# zb_pic16f887.net
KiCad netlist of a schematic drawn in Altium Designer
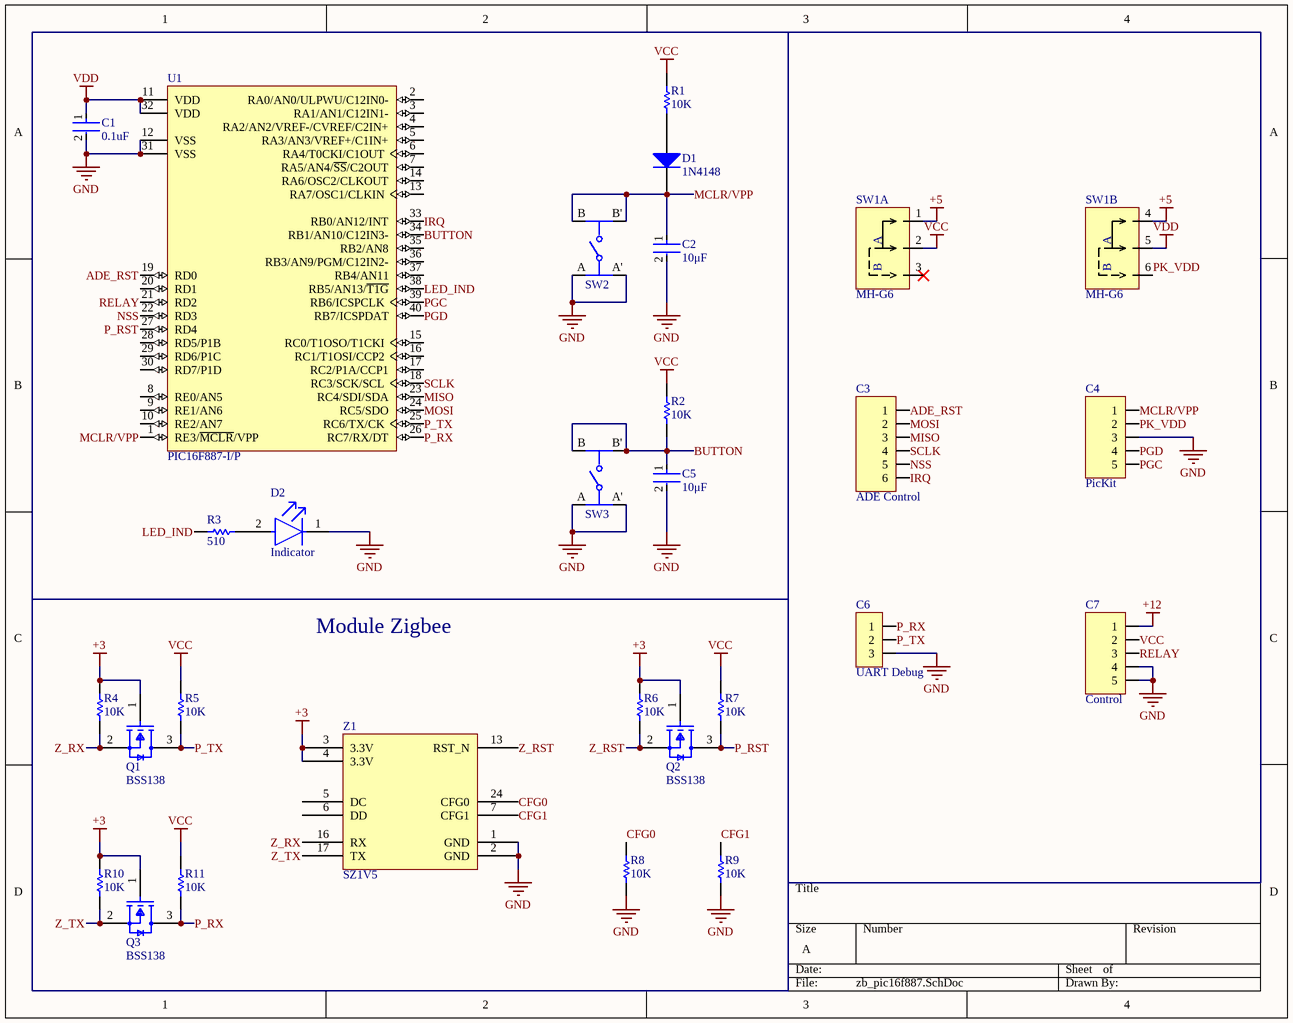
[diagram p0: zb_pic16f887.SchDoc]

(export (version "E")
  (design (tool "Eeschema 10.0.6"))
  (components
    (comp (ref "C1")
      (value "0.1uF")
      (footprint "FP-0603-L_1_6_0_15-W_0_81-IPC_A")
      (description "General Purpose Ceramic Capacitor, 0603, 100nF, 10%, X7R, 15%, 50V")
      (fields (field (name "TOLERANCE") "10%") (field (name "VOLTAGE") "50V"))
      (libsource (lib "Altium Content Vault") (part "02cd4be3c70576c341d710602a673aa"))
    )
    (comp (ref "C2")
      (value "10μF")
      (footprint "FP-0603-L_1_6_0_15-W_0_81-IPC_A")
      (description "General Purpose Ceramic Capacitor, 0603, 100nF, 10%, X7R, 15%, 50V")
      (fields (field (name "TOLERANCE") "10%") (field (name "VOLTAGE") "50V"))
      (libsource (lib "Altium Content Vault") (part "02cd4be3c70576c341d710602a673aa"))
    )
    (comp (ref "C3")
      (value "ADE Control")
      (footprint "JP6-D1T")
      (description "WR-PHD 2.54 mm Angled Socket Header")
      (fields
        (field (name "MANUFACTURER") "Würth Elektronik eiSos GmbH")
        (field (name "PARTNO") "613006143121")
        (field (name "CREATED BY") "Karrer Zheng")
      )
      (libsource (lib "TechMT.VN_Lib_Project v2") (part "JP6"))
    )
    (comp (ref "C4")
      (value "PicKit")
      (footprint "JP5-D1C")
      (description "WR-PHD 2.54 mm Angled Socket Header")
      (fields
        (field (name "MANUFACTURER") "Würth Elektronik eiSos GmbH")
        (field (name "PARTNO") "613005143121")
        (field (name "CREATED BY") "Karrer Zheng")
      )
      (libsource (lib "TechMT.VN_Lib_Project v2") (part "JP5"))
    )
    (comp (ref "C5")
      (value "10μF")
      (footprint "FP-0603-L_1_6_0_15-W_0_81-IPC_A")
      (description "General Purpose Ceramic Capacitor, 0603, 100nF, 10%, X7R, 15%, 50V")
      (fields (field (name "TOLERANCE") "10%") (field (name "VOLTAGE") "50V"))
      (libsource (lib "Altium Content Vault") (part "02cd4be3c70576c341d710602a673aa"))
    )
    (comp (ref "C6")
      (value "UART Debug")
      (footprint "JP3-D1C")
      (description "WR-PHD 2.54 mm Angled Socket Header")
      (fields
        (field (name "MANUFACTURER") "Würth Elektronik eiSos GmbH")
        (field (name "PARTNO") "613003143121")
        (field (name "CREATED BY") "Karrer Zheng")
      )
      (libsource (lib "TechMT.VN_Lib_Project v2") (part "JP3"))
    )
    (comp (ref "C7")
      (value "Control")
      (footprint "JP5-D1T")
      (description "WR-PHD 2.54 mm Angled Socket Header")
      (fields
        (field (name "MANUFACTURER") "Würth Elektronik eiSos GmbH")
        (field (name "PARTNO") "613005143121")
        (field (name "CREATED BY") "Karrer Zheng")
      )
      (libsource (lib "TechMT.VN_Lib_Project v2") (part "JP5"))
    )
    (comp (ref "D1")
      (value "1N4148")
      (footprint "NXP-SOD27-2_V")
      (description "High-speed Diode, 100 V, 450 mA, 2-Pin SOD27, RoHS")
      (fields (field (name "MANUFACTURER") "NXP Semiconductors"))
      (libsource (lib "Altium Content Vault") (part "NXP-A1K2-2"))
    )
    (comp (ref "D2")
      (value "Indicator")
      (footprint "FP-HLMP-4700-MFG")
      (description "LED RED DIFFUSED T-1 3/4 T/H")
      (fields
        (field (name "OCTOPART") "https://octopart.com/hlmp-4700-broadcom-71130526")
        (field (name "MANUFACTURER") "Broadcom")
      )
      (libsource (lib "Altium Content Vault") (part "8706943c75ba83719d021d2fdc84c58"))
    )
    (comp (ref "Q1")
      (value "BSS138")
      (footprint "FP-318-08-IPC_B")
      (description "MOSFET N-CH 50V 220MA SOT-23")
      (libsource (lib "Altium Content Vault") (part "3b9c635fedb024a5347a57b145af9cc"))
    )
    (comp (ref "Q2")
      (value "BSS138")
      (footprint "FP-318-08-IPC_B")
      (description "MOSFET N-CH 50V 220MA SOT-23")
      (libsource (lib "Altium Content Vault") (part "3b9c635fedb024a5347a57b145af9cc"))
    )
    (comp (ref "Q3")
      (value "BSS138")
      (footprint "FP-318-08-IPC_B")
      (description "MOSFET N-CH 50V 220MA SOT-23")
      (libsource (lib "Altium Content Vault") (part "3b9c635fedb024a5347a57b145af9cc"))
    )
    (comp (ref "R1")
      (value "10K")
      (footprint "RESC1609X55X30ML15T15")
      (description "Chip Resistor, 10 KOhm, +/- 1%, 0.1 W, -55 to 155 degC, 0603 (1608 Metric), RoHS, Tape and Reel")
      (fields (field (name "TOLERANCE") "1%") (field (name "MANUFACTURER") "Panasonic"))
      (libsource (lib "Altium Content Vault") (part "RES-2"))
    )
    (comp (ref "R2")
      (value "10K")
      (footprint "RESC1609X55X30ML15T15")
      (description "Chip Resistor, 10 KOhm, +/- 1%, 0.1 W, -55 to 155 degC, 0603 (1608 Metric), RoHS, Tape and Reel")
      (fields (field (name "TOLERANCE") "1%") (field (name "MANUFACTURER") "Panasonic"))
      (libsource (lib "Altium Content Vault") (part "RES-2"))
    )
    (comp (ref "R3")
      (value "510")
      (footprint "RESC1609X55X30ML15T15")
      (description "Chip Resistor, 10 KOhm, +/- 1%, 0.1 W, -55 to 155 degC, 0603 (1608 Metric), RoHS, Tape and Reel")
      (fields (field (name "TOLERANCE") "1%") (field (name "MANUFACTURER") "Panasonic"))
      (libsource (lib "Altium Content Vault") (part "RES-2"))
    )
    (comp (ref "R4")
      (value "10K")
      (footprint "RESC1609X55X30ML15T15")
      (description "Chip Resistor, 10 KOhm, +/- 1%, 0.1 W, -55 to 155 degC, 0603 (1608 Metric), RoHS, Tape and Reel")
      (fields (field (name "TOLERANCE") "1%") (field (name "MANUFACTURER") "Panasonic"))
      (libsource (lib "Altium Content Vault") (part "RES-2"))
    )
    (comp (ref "R5")
      (value "10K")
      (footprint "RESC1609X55X30ML15T15")
      (description "Chip Resistor, 10 KOhm, +/- 1%, 0.1 W, -55 to 155 degC, 0603 (1608 Metric), RoHS, Tape and Reel")
      (fields (field (name "TOLERANCE") "1%") (field (name "MANUFACTURER") "Panasonic"))
      (libsource (lib "Altium Content Vault") (part "RES-2"))
    )
    (comp (ref "R6")
      (value "10K")
      (footprint "RESC1609X55X30ML15T15")
      (description "Chip Resistor, 10 KOhm, +/- 1%, 0.1 W, -55 to 155 degC, 0603 (1608 Metric), RoHS, Tape and Reel")
      (fields (field (name "TOLERANCE") "1%") (field (name "MANUFACTURER") "Panasonic"))
      (libsource (lib "Altium Content Vault") (part "RES-2"))
    )
    (comp (ref "R7")
      (value "10K")
      (footprint "RESC1609X55X30ML15T15")
      (description "Chip Resistor, 10 KOhm, +/- 1%, 0.1 W, -55 to 155 degC, 0603 (1608 Metric), RoHS, Tape and Reel")
      (fields (field (name "TOLERANCE") "1%") (field (name "MANUFACTURER") "Panasonic"))
      (libsource (lib "Altium Content Vault") (part "RES-2"))
    )
    (comp (ref "R8")
      (value "10K")
      (footprint "RESC1609X55X30ML15T15")
      (description "Chip Resistor, 10 KOhm, +/- 1%, 0.1 W, -55 to 155 degC, 0603 (1608 Metric), RoHS, Tape and Reel")
      (fields (field (name "TOLERANCE") "1%") (field (name "MANUFACTURER") "Panasonic"))
      (libsource (lib "Altium Content Vault") (part "RES-2"))
    )
    (comp (ref "R9")
      (value "10K")
      (footprint "RESC1609X55X30ML15T15")
      (description "Chip Resistor, 10 KOhm, +/- 1%, 0.1 W, -55 to 155 degC, 0603 (1608 Metric), RoHS, Tape and Reel")
      (fields (field (name "TOLERANCE") "1%") (field (name "MANUFACTURER") "Panasonic"))
      (libsource (lib "Altium Content Vault") (part "RES-2"))
    )
    (comp (ref "R10")
      (value "10K")
      (footprint "RESC1609X55X30ML15T15")
      (description "Chip Resistor, 10 KOhm, +/- 1%, 0.1 W, -55 to 155 degC, 0603 (1608 Metric), RoHS, Tape and Reel")
      (fields (field (name "TOLERANCE") "1%") (field (name "MANUFACTURER") "Panasonic"))
      (libsource (lib "Altium Content Vault") (part "RES-2"))
    )
    (comp (ref "R11")
      (value "10K")
      (footprint "RESC1609X55X30ML15T15")
      (description "Chip Resistor, 10 KOhm, +/- 1%, 0.1 W, -55 to 155 degC, 0603 (1608 Metric), RoHS, Tape and Reel")
      (fields (field (name "TOLERANCE") "1%") (field (name "MANUFACTURER") "Panasonic"))
      (libsource (lib "Altium Content Vault") (part "RES-2"))
    )
    (comp (ref "SW1")
      (value "MH-G6")
      (footprint "MH-G6")
      (description "6-pin switch MH-G6 2.54mm")
      (libsource (lib "MH-G6") (part "MH-G6"))
    )
    (comp (ref "SW2")
      (value "RESET")
      (footprint "FP-EVQ-PAG05R-MFG")
      (description "SWITCH TACTILE SPST-NO 0.02A 15V")
      (libsource (lib "Altium Content Vault") (part "841f23923f71b23f3ea0ab5dfb78dcc"))
    )
    (comp (ref "SW3")
      (value "Button")
      (footprint "FP-EVQ-PAG05R-MFG")
      (description "SWITCH TACTILE SPST-NO 0.02A 15V")
      (libsource (lib "Altium Content Vault") (part "841f23923f71b23f3ea0ab5dfb78dcc"))
    )
    (comp (ref "U1")
      (value "PIC16F887-I/P")
      (footprint "PDIP600-P40")
      (libsource (lib "Altium Content Vault") (part "MC-8B-16F884-IL40"))
    )
    (comp (ref "Z1")
      (value "SZ1V5")
      (footprint "SZ1V5 PINOUT MODULE")
      (libsource (lib "SZ1V5") (part "SZ1V5_Alt"))
    )
  )
  (nets
    (net (code "1") (name "+3") (class "Default")
      (node (ref "Q1") (pin "1") (pinfunction "G_1") (pintype "passive"))
      (node (ref "Q2") (pin "1") (pinfunction "G_1") (pintype "passive"))
      (node (ref "Q3") (pin "1") (pinfunction "G_1") (pintype "passive"))
      (node (ref "R10") (pin "2") (pinfunction "2_2") (pintype "passive"))
      (node (ref "R4") (pin "2") (pinfunction "2_2") (pintype "passive"))
      (node (ref "R6") (pin "2") (pinfunction "2_2") (pintype "passive"))
      (node (ref "Z1") (pin "3") (pinfunction "3.3V_3") (pintype "passive"))
      (node (ref "Z1") (pin "4") (pinfunction "3.3V_4") (pintype "passive"))
    )
    (net (code "2") (name "+5") (class "Default")
      (node (ref "SW1") (pin "1") (pinfunction "A_1") (pintype "passive"))
      (node (ref "SW1") (pin "4") (pinfunction "A_4") (pintype "passive"))
    )
    (net (code "3") (name "+12") (class "Default")
      (node (ref "C7") (pin "1") (pinfunction "1_1") (pintype "passive"))
    )
    (net (code "4") (name "/ADE_RST") (class "Default")
      (node (ref "C3") (pin "1") (pinfunction "1_1") (pintype "passive"))
      (node (ref "U1") (pin "19") (pinfunction "RD0_19") (pintype "bidirectional"))
    )
    (net (code "5") (name "/BUTTON") (class "Default")
      (node (ref "C5") (pin "1") (pinfunction "1_1") (pintype "passive"))
      (node (ref "R2") (pin "1") (pinfunction "1_1") (pintype "passive"))
      (node (ref "SW3") (pin "B") (pinfunction "B_B") (pintype "passive"))
      (node (ref "SW3") (pin "B'") (pinfunction "B'_B'") (pintype "passive"))
      (node (ref "U1") (pin "34") (pinfunction "RB1/AN10/C12IN3-_34") (pintype "bidirectional"))
    )
    (net (code "6") (name "/CFG0") (class "Default")
      (node (ref "R8") (pin "2") (pinfunction "2_2") (pintype "passive"))
      (node (ref "Z1") (pin "24") (pinfunction "CFG0_24") (pintype "passive"))
    )
    (net (code "7") (name "/CFG1") (class "Default")
      (node (ref "R9") (pin "2") (pinfunction "2_2") (pintype "passive"))
      (node (ref "Z1") (pin "7") (pinfunction "CFG1_7") (pintype "passive"))
    )
    (net (code "8") (name "/IRQ") (class "Default")
      (node (ref "C3") (pin "6") (pinfunction "6_6") (pintype "passive"))
      (node (ref "U1") (pin "33") (pinfunction "RB0/AN12/INT_33") (pintype "bidirectional"))
    )
    (net (code "9") (name "/LED_IND") (class "Default")
      (node (ref "R3") (pin "2") (pinfunction "2_2") (pintype "passive"))
      (node (ref "U1") (pin "38") (pinfunction "RB5/AN13/~{T1G}_38") (pintype "bidirectional"))
    )
    (net (code "10") (name "/MCLR{slash}VPP") (class "Default")
      (node (ref "C2") (pin "1") (pinfunction "1_1") (pintype "passive"))
      (node (ref "C4") (pin "1") (pinfunction "1_1") (pintype "passive"))
      (node (ref "D1") (pin "2") (pinfunction "K_2") (pintype "passive"))
      (node (ref "SW2") (pin "B") (pinfunction "B_B") (pintype "passive"))
      (node (ref "SW2") (pin "B'") (pinfunction "B'_B'") (pintype "passive"))
      (node (ref "U1") (pin "1") (pinfunction "RE3/~{MCLR}/VPP_1") (pintype "bidirectional"))
    )
    (net (code "11") (name "/MISO") (class "Default")
      (node (ref "C3") (pin "3") (pinfunction "3_3") (pintype "passive"))
      (node (ref "U1") (pin "23") (pinfunction "RC4/SDI/SDA_23") (pintype "bidirectional"))
    )
    (net (code "12") (name "/MOSI") (class "Default")
      (node (ref "C3") (pin "2") (pinfunction "2_2") (pintype "passive"))
      (node (ref "U1") (pin "24") (pinfunction "RC5/SDO_24") (pintype "bidirectional"))
    )
    (net (code "13") (name "/NSS") (class "Default")
      (node (ref "C3") (pin "5") (pinfunction "5_5") (pintype "passive"))
      (node (ref "U1") (pin "22") (pinfunction "RD3_22") (pintype "bidirectional"))
    )
    (net (code "14") (name "/PGC") (class "Default")
      (node (ref "C4") (pin "5") (pinfunction "5_5") (pintype "passive"))
      (node (ref "U1") (pin "39") (pinfunction "RB6/ICSPCLK_39") (pintype "bidirectional"))
    )
    (net (code "15") (name "/PGD") (class "Default")
      (node (ref "C4") (pin "4") (pinfunction "4_4") (pintype "passive"))
      (node (ref "U1") (pin "40") (pinfunction "RB7/ICSPDAT_40") (pintype "bidirectional"))
    )
    (net (code "16") (name "/PK_VDD") (class "Default")
      (node (ref "C4") (pin "2") (pinfunction "2_2") (pintype "passive"))
      (node (ref "SW1") (pin "6") (pinfunction "B_6") (pintype "passive"))
    )
    (net (code "17") (name "/P_RST") (class "Default")
      (node (ref "Q2") (pin "3") (pinfunction "D_3") (pintype "passive"))
      (node (ref "R7") (pin "1") (pinfunction "1_1") (pintype "passive"))
      (node (ref "U1") (pin "27") (pinfunction "RD4_27") (pintype "bidirectional"))
    )
    (net (code "18") (name "/P_RX") (class "Default")
      (node (ref "C6") (pin "1") (pinfunction "1_1") (pintype "passive"))
      (node (ref "Q3") (pin "3") (pinfunction "D_3") (pintype "passive"))
      (node (ref "R11") (pin "1") (pinfunction "1_1") (pintype "passive"))
      (node (ref "U1") (pin "26") (pinfunction "RC7/RX/DT_26") (pintype "bidirectional"))
    )
    (net (code "19") (name "/P_TX") (class "Default")
      (node (ref "C6") (pin "2") (pinfunction "2_2") (pintype "passive"))
      (node (ref "Q1") (pin "3") (pinfunction "D_3") (pintype "passive"))
      (node (ref "R5") (pin "1") (pinfunction "1_1") (pintype "passive"))
      (node (ref "U1") (pin "25") (pinfunction "RC6/TX/CK_25") (pintype "bidirectional"))
    )
    (net (code "20") (name "/RELAY") (class "Default")
      (node (ref "C7") (pin "3") (pinfunction "3_3") (pintype "passive"))
      (node (ref "U1") (pin "21") (pinfunction "RD2_21") (pintype "bidirectional"))
    )
    (net (code "21") (name "/SCLK") (class "Default")
      (node (ref "C3") (pin "4") (pinfunction "4_4") (pintype "passive"))
      (node (ref "U1") (pin "18") (pinfunction "RC3/SCK/SCL_18") (pintype "bidirectional"))
    )
    (net (code "22") (name "/Z_RST") (class "Default")
      (node (ref "Q2") (pin "2") (pinfunction "S_2") (pintype "passive"))
      (node (ref "R6") (pin "1") (pinfunction "1_1") (pintype "passive"))
      (node (ref "Z1") (pin "13") (pinfunction "RST_N_13") (pintype "passive"))
    )
    (net (code "23") (name "/Z_RX") (class "Default")
      (node (ref "Q1") (pin "2") (pinfunction "S_2") (pintype "passive"))
      (node (ref "R4") (pin "1") (pinfunction "1_1") (pintype "passive"))
      (node (ref "Z1") (pin "16") (pinfunction "RX_16") (pintype "passive"))
    )
    (net (code "24") (name "/Z_TX") (class "Default")
      (node (ref "Q3") (pin "2") (pinfunction "S_2") (pintype "passive"))
      (node (ref "R10") (pin "1") (pinfunction "1_1") (pintype "passive"))
      (node (ref "Z1") (pin "17") (pinfunction "TX_17") (pintype "passive"))
    )
    (net (code "25") (name "GND") (class "Default")
      (node (ref "C1") (pin "2") (pinfunction "2_2") (pintype "passive"))
      (node (ref "C2") (pin "2") (pinfunction "2_2") (pintype "passive"))
      (node (ref "C4") (pin "3") (pinfunction "3_3") (pintype "passive"))
      (node (ref "C5") (pin "2") (pinfunction "2_2") (pintype "passive"))
      (node (ref "C6") (pin "3") (pinfunction "3_3") (pintype "passive"))
      (node (ref "C7") (pin "4") (pinfunction "4_4") (pintype "passive"))
      (node (ref "C7") (pin "5") (pinfunction "5_5") (pintype "passive"))
      (node (ref "D2") (pin "1") (pinfunction "C_1") (pintype "passive"))
      (node (ref "R8") (pin "1") (pinfunction "1_1") (pintype "passive"))
      (node (ref "R9") (pin "1") (pinfunction "1_1") (pintype "passive"))
      (node (ref "SW2") (pin "A") (pinfunction "A_A") (pintype "passive"))
      (node (ref "SW2") (pin "A'") (pinfunction "A'_A'") (pintype "passive"))
      (node (ref "SW3") (pin "A") (pinfunction "A_A") (pintype "passive"))
      (node (ref "SW3") (pin "A'") (pinfunction "A'_A'") (pintype "passive"))
      (node (ref "U1") (pin "12") (pinfunction "VSS_12") (pintype "power_in"))
      (node (ref "U1") (pin "31") (pinfunction "VSS_31") (pintype "power_in"))
      (node (ref "Z1") (pin "1") (pinfunction "GND_1") (pintype "passive"))
      (node (ref "Z1") (pin "2") (pinfunction "GND_2") (pintype "passive"))
    )
    (net (code "26") (name "Net-(D1-A)") (class "Default")
      (node (ref "D1") (pin "1") (pinfunction "A_1") (pintype "passive"))
      (node (ref "R1") (pin "1") (pinfunction "1_1") (pintype "passive"))
    )
    (net (code "27") (name "Net-(D2-A)") (class "Default")
      (node (ref "D2") (pin "2") (pinfunction "A_2") (pintype "passive"))
      (node (ref "R3") (pin "1") (pinfunction "1_1") (pintype "passive"))
    )
    (net (code "28") (name "VCC") (class "Default")
      (node (ref "C7") (pin "2") (pinfunction "2_2") (pintype "passive"))
      (node (ref "R1") (pin "2") (pinfunction "2_2") (pintype "passive"))
      (node (ref "R11") (pin "2") (pinfunction "2_2") (pintype "passive"))
      (node (ref "R2") (pin "2") (pinfunction "2_2") (pintype "passive"))
      (node (ref "R5") (pin "2") (pinfunction "2_2") (pintype "passive"))
      (node (ref "R7") (pin "2") (pinfunction "2_2") (pintype "passive"))
      (node (ref "SW1") (pin "2") (pinfunction "COM_2") (pintype "passive"))
    )
    (net (code "29") (name "VDD") (class "Default")
      (node (ref "C1") (pin "1") (pinfunction "1_1") (pintype "passive"))
      (node (ref "SW1") (pin "5") (pinfunction "COM_5") (pintype "passive"))
      (node (ref "U1") (pin "11") (pinfunction "VDD_11") (pintype "power_in"))
      (node (ref "U1") (pin "32") (pinfunction "VDD_32") (pintype "power_in"))
    )
    (net (code "30") (name "unconnected-(SW1A-B-Pad3)") (class "Default")
      (node (ref "SW1") (pin "3") (pinfunction "B_3") (pintype "passive+no_connect"))
    )
    (net (code "31") (name "unconnected-(U1-RA0{slash}AN0{slash}ULPWU{slash}C12IN0--Pad2)") (class "Default")
      (node (ref "U1") (pin "2") (pinfunction "RA0/AN0/ULPWU/C12IN0-_2") (pintype "bidirectional"))
    )
    (net (code "32") (name "unconnected-(U1-RA1{slash}AN1{slash}C12IN1--Pad3)") (class "Default")
      (node (ref "U1") (pin "3") (pinfunction "RA1/AN1/C12IN1-_3") (pintype "bidirectional"))
    )
    (net (code "33") (name "unconnected-(U1-RA2{slash}AN2{slash}VREF-{slash}CVREF{slash}C2IN+-Pad4)") (class "Default")
      (node (ref "U1") (pin "4") (pinfunction "RA2/AN2/VREF-/CVREF/C2IN+_4") (pintype "bidirectional"))
    )
    (net (code "34") (name "unconnected-(U1-RA3{slash}AN3{slash}VREF+{slash}C1IN+-Pad5)") (class "Default")
      (node (ref "U1") (pin "5") (pinfunction "RA3/AN3/VREF+/C1IN+_5") (pintype "bidirectional"))
    )
    (net (code "35") (name "unconnected-(U1-RA4{slash}T0CKI{slash}C1OUT-Pad6)") (class "Default")
      (node (ref "U1") (pin "6") (pinfunction "RA4/T0CKI/C1OUT_6") (pintype "bidirectional"))
    )
    (net (code "36") (name "unconnected-(U1-RA5{slash}AN4{slash}~{SS}{slash}C2OUT-Pad7)") (class "Default")
      (node (ref "U1") (pin "7") (pinfunction "RA5/AN4/~{SS}/C2OUT_7") (pintype "bidirectional"))
    )
    (net (code "37") (name "unconnected-(U1-RA6{slash}OSC2{slash}CLKOUT-Pad14)") (class "Default")
      (node (ref "U1") (pin "14") (pinfunction "RA6/OSC2/CLKOUT_14") (pintype "bidirectional"))
    )
    (net (code "38") (name "unconnected-(U1-RA7{slash}OSC1{slash}CLKIN-Pad13)") (class "Default")
      (node (ref "U1") (pin "13") (pinfunction "RA7/OSC1/CLKIN_13") (pintype "bidirectional"))
    )
    (net (code "39") (name "unconnected-(U1-RB2{slash}AN8-Pad35)") (class "Default")
      (node (ref "U1") (pin "35") (pinfunction "RB2/AN8_35") (pintype "bidirectional"))
    )
    (net (code "40") (name "unconnected-(U1-RB3{slash}AN9{slash}PGM{slash}C12IN2--Pad36)") (class "Default")
      (node (ref "U1") (pin "36") (pinfunction "RB3/AN9/PGM/C12IN2-_36") (pintype "bidirectional"))
    )
    (net (code "41") (name "unconnected-(U1-RB4{slash}AN11-Pad37)") (class "Default")
      (node (ref "U1") (pin "37") (pinfunction "RB4/AN11_37") (pintype "bidirectional"))
    )
    (net (code "42") (name "unconnected-(U1-RC0{slash}T1OSO{slash}T1CKI-Pad15)") (class "Default")
      (node (ref "U1") (pin "15") (pinfunction "RC0/T1OSO/T1CKI_15") (pintype "bidirectional"))
    )
    (net (code "43") (name "unconnected-(U1-RC1{slash}T1OSI{slash}CCP2-Pad16)") (class "Default")
      (node (ref "U1") (pin "16") (pinfunction "RC1/T1OSI/CCP2_16") (pintype "bidirectional"))
    )
    (net (code "44") (name "unconnected-(U1-RC2{slash}P1A{slash}CCP1-Pad17)") (class "Default")
      (node (ref "U1") (pin "17") (pinfunction "RC2/P1A/CCP1_17") (pintype "bidirectional"))
    )
    (net (code "45") (name "unconnected-(U1-RD1-Pad20)") (class "Default")
      (node (ref "U1") (pin "20") (pinfunction "RD1_20") (pintype "bidirectional"))
    )
    (net (code "46") (name "unconnected-(U1-RD5{slash}P1B-Pad28)") (class "Default")
      (node (ref "U1") (pin "28") (pinfunction "RD5/P1B_28") (pintype "bidirectional"))
    )
    (net (code "47") (name "unconnected-(U1-RD6{slash}P1C-Pad29)") (class "Default")
      (node (ref "U1") (pin "29") (pinfunction "RD6/P1C_29") (pintype "bidirectional"))
    )
    (net (code "48") (name "unconnected-(U1-RD7{slash}P1D-Pad30)") (class "Default")
      (node (ref "U1") (pin "30") (pinfunction "RD7/P1D_30") (pintype "bidirectional"))
    )
    (net (code "49") (name "unconnected-(U1-RE0{slash}AN5-Pad8)") (class "Default")
      (node (ref "U1") (pin "8") (pinfunction "RE0/AN5_8") (pintype "bidirectional"))
    )
    (net (code "50") (name "unconnected-(U1-RE1{slash}AN6-Pad9)") (class "Default")
      (node (ref "U1") (pin "9") (pinfunction "RE1/AN6_9") (pintype "bidirectional"))
    )
    (net (code "51") (name "unconnected-(U1-RE2{slash}AN7-Pad10)") (class "Default")
      (node (ref "U1") (pin "10") (pinfunction "RE2/AN7_10") (pintype "bidirectional"))
    )
    (net (code "52") (name "unconnected-(Z1-DC-Pad5)") (class "Default")
      (node (ref "Z1") (pin "5") (pinfunction "DC_5") (pintype "passive"))
    )
    (net (code "53") (name "unconnected-(Z1-DD-Pad6)") (class "Default")
      (node (ref "Z1") (pin "6") (pinfunction "DD_6") (pintype "passive"))
    )
  )
)
